# Sheet1.net
KiCad netlist of a schematic drawn in Altium Designer
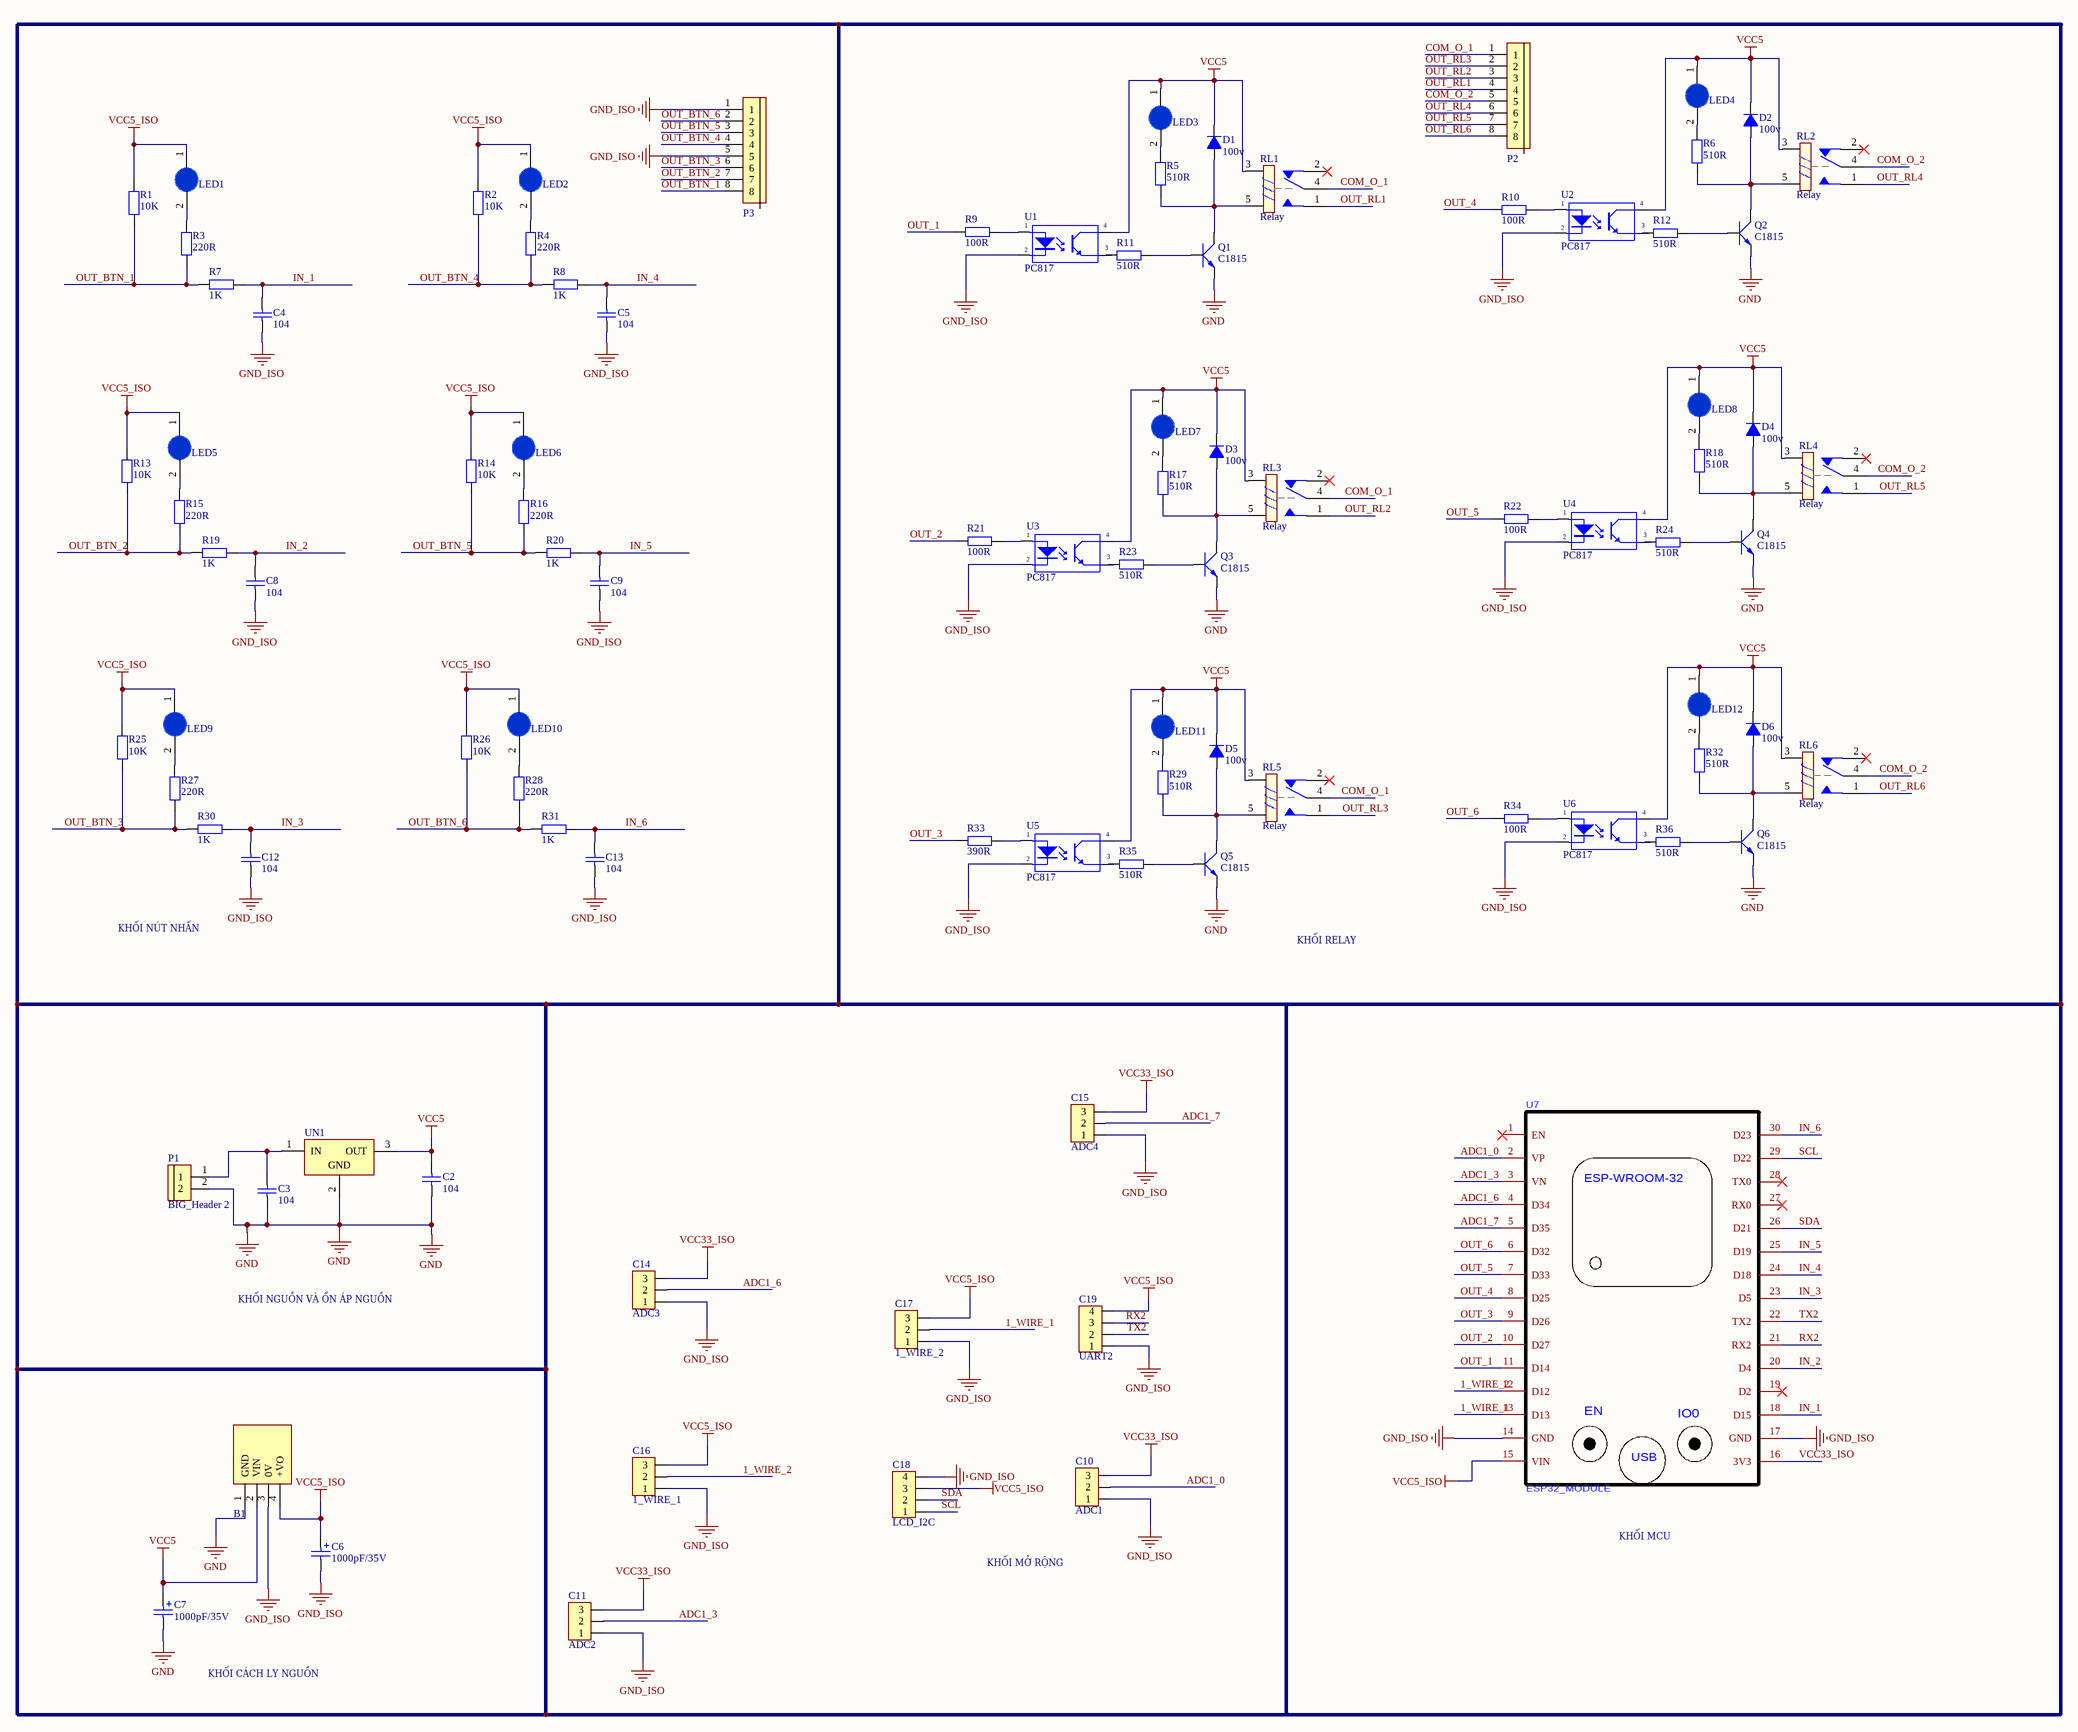
[diagram p0: Sheet1.SchDoc]

(export (version "E")
  (design (tool "Eeschema 10.0.6"))
  (components
    (comp (ref "B1")
      (value "B0505S1W")
      (footprint "B0505S1W")
      (description "Power Supply")
      (fields (field (name "MANUFACTURER_PART_NUMBER") "B0505S-1W"))
      (libsource (lib "myLib_v1") (part "B0505S1W"))
    )
    (comp (ref "C2")
      (value "104")
      (footprint "tu gom")
      (description "Cắm")
      (libsource (lib "Altium_Lib_by_KhueNguyenCreator") (part "Tu gom 104 50V"))
    )
    (comp (ref "C3")
      (value "104")
      (footprint "tu gom")
      (description "Cắm")
      (libsource (lib "Altium_Lib_by_KhueNguyenCreator") (part "Tu gom 104 50V"))
    )
    (comp (ref "C4")
      (value "104")
      (footprint "tu gom")
      (description "Cắm")
      (libsource (lib "Altium_Lib_by_KhueNguyenCreator") (part "Tu gom 104 50V"))
    )
    (comp (ref "C5")
      (value "104")
      (footprint "tu gom")
      (description "Cắm")
      (libsource (lib "Altium_Lib_by_KhueNguyenCreator") (part "Tu gom 104 50V"))
    )
    (comp (ref "C6")
      (value "1000pF/35V")
      (footprint "CP2/5")
      (description "Polarized Capacitor (Surface Mount)")
      (fields (field (name "Comment") "Cap Pol3") (field (name "PUBLISHER") "Altium Limited"))
      (libsource (lib "myLib_v1") (part "Cap Pol3"))
    )
    (comp (ref "C7")
      (value "1000pF/35V")
      (footprint "CP2/5")
      (description "Polarized Capacitor (Surface Mount)")
      (fields (field (name "Comment") "Cap Pol3") (field (name "PUBLISHER") "Altium Limited"))
      (libsource (lib "myLib_v1") (part "Cap Pol3"))
    )
    (comp (ref "C8")
      (value "104")
      (footprint "tu gom")
      (description "Cắm")
      (libsource (lib "Altium_Lib_by_KhueNguyenCreator") (part "Tu gom 104 50V"))
    )
    (comp (ref "C9")
      (value "104")
      (footprint "tu gom")
      (description "Cắm")
      (libsource (lib "Altium_Lib_by_KhueNguyenCreator") (part "Tu gom 104 50V"))
    )
    (comp (ref "C10")
      (value "ADC1")
      (footprint "Header3")
      (description "Header IDC, 3 x 1 Pin Vertical 2.54mm Pitch (Non-Boxed, Male)")
      (fields
        (field (name "MANUFACTURER") "Würth Elektronik eiSos GmbH")
        (field (name "PARTNO") "613002143121")
        (field (name "CREATED BY") "Karrer Zheng")
      )
      (libsource (lib "myLib_v1") (part "Header3"))
    )
    (comp (ref "C11")
      (value "ADC2")
      (footprint "Header3")
      (description "Header IDC, 3 x 1 Pin Vertical 2.54mm Pitch (Non-Boxed, Male)")
      (fields
        (field (name "MANUFACTURER") "Würth Elektronik eiSos GmbH")
        (field (name "PARTNO") "613002143121")
        (field (name "CREATED BY") "Karrer Zheng")
      )
      (libsource (lib "myLib_v1") (part "Header3"))
    )
    (comp (ref "C12")
      (value "104")
      (footprint "tu gom")
      (description "Cắm")
      (libsource (lib "Altium_Lib_by_KhueNguyenCreator") (part "Tu gom 104 50V"))
    )
    (comp (ref "C13")
      (value "104")
      (footprint "tu gom")
      (description "Cắm")
      (libsource (lib "Altium_Lib_by_KhueNguyenCreator") (part "Tu gom 104 50V"))
    )
    (comp (ref "C14")
      (value "ADC3")
      (footprint "Header3")
      (description "Header IDC, 3 x 1 Pin Vertical 2.54mm Pitch (Non-Boxed, Male)")
      (fields
        (field (name "MANUFACTURER") "Würth Elektronik eiSos GmbH")
        (field (name "PARTNO") "613002143121")
        (field (name "CREATED BY") "Karrer Zheng")
      )
      (libsource (lib "myLib_v1") (part "Header3"))
    )
    (comp (ref "C15")
      (value "ADC4")
      (footprint "Header3")
      (description "Header IDC, 3 x 1 Pin Vertical 2.54mm Pitch (Non-Boxed, Male)")
      (fields
        (field (name "MANUFACTURER") "Würth Elektronik eiSos GmbH")
        (field (name "PARTNO") "613002143121")
        (field (name "CREATED BY") "Karrer Zheng")
      )
      (libsource (lib "myLib_v1") (part "Header3"))
    )
    (comp (ref "C16")
      (value "1_WIRE_1")
      (footprint "Header3")
      (description "Header IDC, 3 x 1 Pin Vertical 2.54mm Pitch (Non-Boxed, Male)")
      (fields
        (field (name "MANUFACTURER") "Würth Elektronik eiSos GmbH")
        (field (name "PARTNO") "613002143121")
        (field (name "CREATED BY") "Karrer Zheng")
      )
      (libsource (lib "myLib_v1") (part "Header3"))
    )
    (comp (ref "C17")
      (value "1_WIRE_2")
      (footprint "Header3")
      (description "Header IDC, 3 x 1 Pin Vertical 2.54mm Pitch (Non-Boxed, Male)")
      (fields
        (field (name "MANUFACTURER") "Würth Elektronik eiSos GmbH")
        (field (name "PARTNO") "613002143121")
        (field (name "CREATED BY") "Karrer Zheng")
      )
      (libsource (lib "myLib_v1") (part "Header3"))
    )
    (comp (ref "C18")
      (value "LCD_I2C")
      (footprint "Header4")
      (description "Header IDC, 4 x 1 Pin Vertical 2.54mm Pitch (Non-Boxed, Male)")
      (fields
        (field (name "MANUFACTURER") "Würth Elektronik eiSos GmbH")
        (field (name "PARTNO") "613002143121")
        (field (name "CREATED BY") "Karrer Zheng")
      )
      (libsource (lib "myLib_v1") (part "Header4"))
    )
    (comp (ref "C19")
      (value "UART2")
      (footprint "Header4")
      (description "Header IDC, 4 x 1 Pin Vertical 2.54mm Pitch (Non-Boxed, Male)")
      (fields
        (field (name "MANUFACTURER") "Würth Elektronik eiSos GmbH")
        (field (name "PARTNO") "613002143121")
        (field (name "CREATED BY") "Karrer Zheng")
      )
      (libsource (lib "myLib_v1") (part "Header4"))
    )
    (comp (ref "D1")
      (value "100v")
      (footprint "DIODE 0.5A")
      (description "Cắm")
      (libsource (lib "Altium_Lib_by_KhueNguyenCreator") (part "Diode 1N4148"))
    )
    (comp (ref "D2")
      (value "100v")
      (footprint "DIODE 0.5A")
      (description "Cắm")
      (libsource (lib "Altium_Lib_by_KhueNguyenCreator") (part "Diode 1N4148"))
    )
    (comp (ref "D3")
      (value "100v")
      (footprint "DIODE 0.5A")
      (description "Cắm")
      (libsource (lib "Altium_Lib_by_KhueNguyenCreator") (part "Diode 1N4148"))
    )
    (comp (ref "D4")
      (value "100v")
      (footprint "DIODE 0.5A")
      (description "Cắm")
      (libsource (lib "Altium_Lib_by_KhueNguyenCreator") (part "Diode 1N4148"))
    )
    (comp (ref "D5")
      (value "100v")
      (footprint "DIODE 0.5A")
      (description "Cắm")
      (libsource (lib "Altium_Lib_by_KhueNguyenCreator") (part "Diode 1N4148"))
    )
    (comp (ref "D6")
      (value "100v")
      (footprint "DIODE 0.5A")
      (description "Cắm")
      (libsource (lib "Altium_Lib_by_KhueNguyenCreator") (part "Diode 1N4148"))
    )
    (comp (ref "LED1")
      (value "LED 3mm")
      (footprint "LED-3MM-BLUE")
      (description "Cắm")
      (libsource (lib "myLib_v1") (part "LED 3mm Xanh Duong"))
    )
    (comp (ref "LED2")
      (value "LED 3mm")
      (footprint "LED-3MM-BLUE")
      (description "Cắm")
      (libsource (lib "myLib_v1") (part "LED 3mm Xanh Duong"))
    )
    (comp (ref "LED3")
      (value "LED 3mm")
      (footprint "LED-3MM-BLUE")
      (description "Cắm")
      (libsource (lib "myLib_v1") (part "LED 3mm Xanh Duong"))
    )
    (comp (ref "LED4")
      (value "LED 3mm")
      (footprint "LED-3MM-BLUE")
      (description "Cắm")
      (libsource (lib "myLib_v1") (part "LED 3mm Xanh Duong"))
    )
    (comp (ref "LED5")
      (value "LED 3mm")
      (footprint "LED-3MM-BLUE")
      (description "Cắm")
      (libsource (lib "myLib_v1") (part "LED 3mm Xanh Duong"))
    )
    (comp (ref "LED6")
      (value "LED 3mm")
      (footprint "LED-3MM-BLUE")
      (description "Cắm")
      (libsource (lib "myLib_v1") (part "LED 3mm Xanh Duong"))
    )
    (comp (ref "LED7")
      (value "LED 3mm")
      (footprint "LED-3MM-BLUE")
      (description "Cắm")
      (libsource (lib "myLib_v1") (part "LED 3mm Xanh Duong"))
    )
    (comp (ref "LED8")
      (value "LED 3mm")
      (footprint "LED-3MM-BLUE")
      (description "Cắm")
      (libsource (lib "myLib_v1") (part "LED 3mm Xanh Duong"))
    )
    (comp (ref "LED9")
      (value "LED 3mm")
      (footprint "LED-3MM-BLUE")
      (description "Cắm")
      (libsource (lib "myLib_v1") (part "LED 3mm Xanh Duong"))
    )
    (comp (ref "LED10")
      (value "LED 3mm")
      (footprint "LED-3MM-BLUE")
      (description "Cắm")
      (libsource (lib "myLib_v1") (part "LED 3mm Xanh Duong"))
    )
    (comp (ref "LED11")
      (value "LED 3mm")
      (footprint "LED-3MM-BLUE")
      (description "Cắm")
      (libsource (lib "myLib_v1") (part "LED 3mm Xanh Duong"))
    )
    (comp (ref "LED12")
      (value "LED 3mm")
      (footprint "LED-3MM-BLUE")
      (description "Cắm")
      (libsource (lib "myLib_v1") (part "LED 3mm Xanh Duong"))
    )
    (comp (ref "P1")
      (value "BIG_Header 2")
      (footprint "BIG_Header 2")
      (libsource (lib "BYTECH_HW_LIB_2019 (1)") (part "BIG_Header 2"))
    )
    (comp (ref "P2")
      (value "BIG Heager 8")
      (footprint "BIG_Header 8")
      (libsource (lib "BYTECH_HW_LIB_2019 (1)") (part "BIG_Header 8"))
    )
    (comp (ref "P3")
      (value "BIG Heager 8")
      (footprint "BIG_Header 8")
      (libsource (lib "BYTECH_HW_LIB_2019 (1)") (part "BIG_Header 8"))
    )
    (comp (ref "Q1")
      (value "C1815")
      (footprint "C1815_cam")
      (description "NPN 600mW, ECB")
      (libsource (lib "myLib_v1") (part "C1815"))
    )
    (comp (ref "Q2")
      (value "C1815")
      (footprint "C1815_cam")
      (description "NPN 600mW, ECB")
      (libsource (lib "myLib_v1") (part "C1815"))
    )
    (comp (ref "Q3")
      (value "C1815")
      (footprint "C1815_cam")
      (description "NPN 600mW, ECB")
      (libsource (lib "myLib_v1") (part "C1815"))
    )
    (comp (ref "Q4")
      (value "C1815")
      (footprint "C1815_cam")
      (description "NPN 600mW, ECB")
      (libsource (lib "myLib_v1") (part "C1815"))
    )
    (comp (ref "Q5")
      (value "C1815")
      (footprint "C1815_cam")
      (description "NPN 600mW, ECB")
      (libsource (lib "myLib_v1") (part "C1815"))
    )
    (comp (ref "Q6")
      (value "C1815")
      (footprint "C1815_cam")
      (description "NPN 600mW, ECB")
      (libsource (lib "myLib_v1") (part "C1815"))
    )
    (comp (ref "R1")
      (value "10K")
      (footprint "R1/4W")
      (description "Resistor 1/4W")
      (libsource (lib "myLib_v1") (part "R1/4W"))
    )
    (comp (ref "R2")
      (value "10K")
      (footprint "R1/4W")
      (description "Resistor 1/4W")
      (libsource (lib "myLib_v1") (part "R1/4W"))
    )
    (comp (ref "R3")
      (value "220R")
      (footprint "R1/4W")
      (description "Resistor 1/4W")
      (libsource (lib "myLib_v1") (part "R1/4W"))
    )
    (comp (ref "R4")
      (value "220R")
      (footprint "R1/4W")
      (description "Resistor 1/4W")
      (libsource (lib "myLib_v1") (part "R1/4W"))
    )
    (comp (ref "R5")
      (value "510R")
      (footprint "R1/4W")
      (description "Resistor 1/4W")
      (libsource (lib "myLib_v1") (part "R1/4W"))
    )
    (comp (ref "R6")
      (value "510R")
      (footprint "R1/4W")
      (description "Resistor 1/4W")
      (libsource (lib "myLib_v1") (part "R1/4W"))
    )
    (comp (ref "R7")
      (value "1K")
      (footprint "R1/4W")
      (description "Resistor 1/4W")
      (libsource (lib "myLib_v1") (part "R1/4W"))
    )
    (comp (ref "R8")
      (value "1K")
      (footprint "R1/4W")
      (description "Resistor 1/4W")
      (libsource (lib "myLib_v1") (part "R1/4W"))
    )
    (comp (ref "R9")
      (value "100R")
      (footprint "R1/4W")
      (description "Resistor 1/4W")
      (libsource (lib "myLib_v1") (part "R1/4W"))
    )
    (comp (ref "R10")
      (value "100R")
      (footprint "R1/4W")
      (description "Resistor 1/4W")
      (libsource (lib "myLib_v1") (part "R1/4W"))
    )
    (comp (ref "R11")
      (value "510R")
      (footprint "R1/4W")
      (description "Resistor 1/4W")
      (libsource (lib "myLib_v1") (part "R1/4W"))
    )
    (comp (ref "R12")
      (value "510R")
      (footprint "R1/4W")
      (description "Resistor 1/4W")
      (libsource (lib "myLib_v1") (part "R1/4W"))
    )
    (comp (ref "R13")
      (value "10K")
      (footprint "R1/4W")
      (description "Resistor 1/4W")
      (libsource (lib "myLib_v1") (part "R1/4W"))
    )
    (comp (ref "R14")
      (value "10K")
      (footprint "R1/4W")
      (description "Resistor 1/4W")
      (libsource (lib "myLib_v1") (part "R1/4W"))
    )
    (comp (ref "R15")
      (value "220R")
      (footprint "R1/4W")
      (description "Resistor 1/4W")
      (libsource (lib "myLib_v1") (part "R1/4W"))
    )
    (comp (ref "R16")
      (value "220R")
      (footprint "R1/4W")
      (description "Resistor 1/4W")
      (libsource (lib "myLib_v1") (part "R1/4W"))
    )
    (comp (ref "R17")
      (value "510R")
      (footprint "R1/4W")
      (description "Resistor 1/4W")
      (libsource (lib "myLib_v1") (part "R1/4W"))
    )
    (comp (ref "R18")
      (value "510R")
      (footprint "R1/4W")
      (description "Resistor 1/4W")
      (libsource (lib "myLib_v1") (part "R1/4W"))
    )
    (comp (ref "R19")
      (value "1K")
      (footprint "R1/4W")
      (description "Resistor 1/4W")
      (libsource (lib "myLib_v1") (part "R1/4W"))
    )
    (comp (ref "R20")
      (value "1K")
      (footprint "R1/4W")
      (description "Resistor 1/4W")
      (libsource (lib "myLib_v1") (part "R1/4W"))
    )
    (comp (ref "R21")
      (value "100R")
      (footprint "R1/4W")
      (description "Resistor 1/4W")
      (libsource (lib "myLib_v1") (part "R1/4W"))
    )
    (comp (ref "R22")
      (value "100R")
      (footprint "R1/4W")
      (description "Resistor 1/4W")
      (libsource (lib "myLib_v1") (part "R1/4W"))
    )
    (comp (ref "R23")
      (value "510R")
      (footprint "R1/4W")
      (description "Resistor 1/4W")
      (libsource (lib "myLib_v1") (part "R1/4W"))
    )
    (comp (ref "R24")
      (value "510R")
      (footprint "R1/4W")
      (description "Resistor 1/4W")
      (libsource (lib "myLib_v1") (part "R1/4W"))
    )
    (comp (ref "R25")
      (value "10K")
      (footprint "R1/4W")
      (description "Resistor 1/4W")
      (libsource (lib "myLib_v1") (part "R1/4W"))
    )
    (comp (ref "R26")
      (value "10K")
      (footprint "R1/4W")
      (description "Resistor 1/4W")
      (libsource (lib "myLib_v1") (part "R1/4W"))
    )
    (comp (ref "R27")
      (value "220R")
      (footprint "R1/4W")
      (description "Resistor 1/4W")
      (libsource (lib "myLib_v1") (part "R1/4W"))
    )
    (comp (ref "R28")
      (value "220R")
      (footprint "R1/4W")
      (description "Resistor 1/4W")
      (libsource (lib "myLib_v1") (part "R1/4W"))
    )
    (comp (ref "R29")
      (value "510R")
      (footprint "R1/4W")
      (description "Resistor 1/4W")
      (libsource (lib "myLib_v1") (part "R1/4W"))
    )
    (comp (ref "R30")
      (value "1K")
      (footprint "R1/4W")
      (description "Resistor 1/4W")
      (libsource (lib "myLib_v1") (part "R1/4W"))
    )
    (comp (ref "R31")
      (value "1K")
      (footprint "R1/4W")
      (description "Resistor 1/4W")
      (libsource (lib "myLib_v1") (part "R1/4W"))
    )
    (comp (ref "R32")
      (value "510R")
      (footprint "R1/4W")
      (description "Resistor 1/4W")
      (libsource (lib "myLib_v1") (part "R1/4W"))
    )
    (comp (ref "R33")
      (value "390R")
      (footprint "R1/4W")
      (description "Resistor 1/4W")
      (libsource (lib "myLib_v1") (part "R1/4W"))
    )
    (comp (ref "R34")
      (value "100R")
      (footprint "R1/4W")
      (description "Resistor 1/4W")
      (libsource (lib "myLib_v1") (part "R1/4W"))
    )
    (comp (ref "R35")
      (value "510R")
      (footprint "R1/4W")
      (description "Resistor 1/4W")
      (libsource (lib "myLib_v1") (part "R1/4W"))
    )
    (comp (ref "R36")
      (value "510R")
      (footprint "R1/4W")
      (description "Resistor 1/4W")
      (libsource (lib "myLib_v1") (part "R1/4W"))
    )
    (comp (ref "RL1")
      (value "Relay")
      (footprint "RELAY_SRA_05VDC_SL_C")
      (description "Relay 5 Chan")
      (libsource (lib "myLib_v1") (part "RL_SRA-05VDC-SL-C"))
    )
    (comp (ref "RL2")
      (value "Relay")
      (footprint "RELAY_SRA_05VDC_SL_C")
      (description "Relay 5 Chan")
      (libsource (lib "myLib_v1") (part "RL_SRA-05VDC-SL-C"))
    )
    (comp (ref "RL3")
      (value "Relay")
      (footprint "RELAY_SRA_05VDC_SL_C")
      (description "Relay 5 Chan")
      (libsource (lib "myLib_v1") (part "RL_SRA-05VDC-SL-C"))
    )
    (comp (ref "RL4")
      (value "Relay")
      (footprint "RELAY_SRA_05VDC_SL_C")
      (description "Relay 5 Chan")
      (libsource (lib "myLib_v1") (part "RL_SRA-05VDC-SL-C"))
    )
    (comp (ref "RL5")
      (value "Relay")
      (footprint "RELAY_SRA_05VDC_SL_C")
      (description "Relay 5 Chan")
      (libsource (lib "myLib_v1") (part "RL_SRA-05VDC-SL-C"))
    )
    (comp (ref "RL6")
      (value "Relay")
      (footprint "RELAY_SRA_05VDC_SL_C")
      (description "Relay 5 Chan")
      (libsource (lib "myLib_v1") (part "RL_SRA-05VDC-SL-C"))
    )
    (comp (ref "U1")
      (value "PC817")
      (footprint "DIP4/W0.3")
      (description "Single Opto")
      (libsource (lib "myLib_v1") (part "PC817"))
    )
    (comp (ref "U2")
      (value "PC817")
      (footprint "DIP4/W0.3")
      (description "Single Opto")
      (libsource (lib "myLib_v1") (part "PC817"))
    )
    (comp (ref "U3")
      (value "PC817")
      (footprint "DIP4/W0.3")
      (description "Single Opto")
      (libsource (lib "myLib_v1") (part "PC817"))
    )
    (comp (ref "U4")
      (value "PC817")
      (footprint "DIP4/W0.3")
      (description "Single Opto")
      (libsource (lib "myLib_v1") (part "PC817"))
    )
    (comp (ref "U5")
      (value "PC817")
      (footprint "DIP4/W0.3")
      (description "Single Opto")
      (libsource (lib "myLib_v1") (part "PC817"))
    )
    (comp (ref "U6")
      (value "PC817")
      (footprint "DIP4/W0.3")
      (description "Single Opto")
      (libsource (lib "myLib_v1") (part "PC817"))
    )
    (comp (ref "U7")
      (value "ESP32_MODULE")
      (footprint "ESP32-WIFIMODULE-FOOTPRINT")
      (libsource (lib "myLib_v1") (part "ESP32_MODULE copy"))
    )
    (comp (ref "UN1")
      (value "L78M05CP")
      (footprint "QTO-220H2")
      (description "Positive Voltage Regulator")
      (fields (field (name "PUBLISHER") "Altium Limited"))
      (libsource (lib "syhaunguyen") (part "L78M05CP"))
    )
  )
  (nets
    (net (code "1") (name "/1_WIRE_1") (class "Default")
      (node (ref "C17") (pin "2") (pinfunction "2_2") (pintype "passive"))
      (node (ref "U7") (pin "13") (pinfunction "D13_13") (pintype "passive"))
    )
    (net (code "2") (name "/1_WIRE_2") (class "Default")
      (node (ref "C16") (pin "2") (pinfunction "2_2") (pintype "passive"))
      (node (ref "U7") (pin "12") (pinfunction "D12_12") (pintype "passive"))
    )
    (net (code "3") (name "/ADC1_0") (class "Default")
      (node (ref "C10") (pin "2") (pinfunction "2_2") (pintype "passive"))
      (node (ref "U7") (pin "2") (pinfunction "VP_2") (pintype "passive"))
    )
    (net (code "4") (name "/ADC1_3") (class "Default")
      (node (ref "C11") (pin "2") (pinfunction "2_2") (pintype "passive"))
      (node (ref "U7") (pin "3") (pinfunction "VN_3") (pintype "passive"))
    )
    (net (code "5") (name "/ADC1_6") (class "Default")
      (node (ref "C14") (pin "2") (pinfunction "2_2") (pintype "passive"))
      (node (ref "U7") (pin "4") (pinfunction "D34_4") (pintype "passive"))
    )
    (net (code "6") (name "/ADC1_7") (class "Default")
      (node (ref "C15") (pin "2") (pinfunction "2_2") (pintype "passive"))
      (node (ref "U7") (pin "5") (pinfunction "D35_5") (pintype "passive"))
    )
    (net (code "7") (name "/COM_O_1") (class "Default")
      (node (ref "P2") (pin "1") (pinfunction "1_1") (pintype "passive"))
      (node (ref "RL1") (pin "4") (pinfunction "4_4") (pintype "passive"))
      (node (ref "RL3") (pin "4") (pinfunction "4_4") (pintype "passive"))
      (node (ref "RL5") (pin "4") (pinfunction "4_4") (pintype "passive"))
    )
    (net (code "8") (name "/COM_O_2") (class "Default")
      (node (ref "P2") (pin "5") (pinfunction "5_5") (pintype "passive"))
      (node (ref "RL2") (pin "4") (pinfunction "4_4") (pintype "passive"))
      (node (ref "RL4") (pin "4") (pinfunction "4_4") (pintype "passive"))
      (node (ref "RL6") (pin "4") (pinfunction "4_4") (pintype "passive"))
    )
    (net (code "9") (name "/IN_1") (class "Default")
      (node (ref "C4") (pin "1") (pinfunction "1_1") (pintype "passive"))
      (node (ref "R7") (pin "1") (pinfunction "1_1") (pintype "passive"))
      (node (ref "U7") (pin "18") (pinfunction "D15_18") (pintype "passive"))
    )
    (net (code "10") (name "/IN_2") (class "Default")
      (node (ref "C8") (pin "1") (pinfunction "1_1") (pintype "passive"))
      (node (ref "R19") (pin "1") (pinfunction "1_1") (pintype "passive"))
      (node (ref "U7") (pin "20") (pinfunction "D4_20") (pintype "passive"))
    )
    (net (code "11") (name "/IN_3") (class "Default")
      (node (ref "C12") (pin "1") (pinfunction "1_1") (pintype "passive"))
      (node (ref "R30") (pin "1") (pinfunction "1_1") (pintype "passive"))
      (node (ref "U7") (pin "23") (pinfunction "D5_23") (pintype "passive"))
    )
    (net (code "12") (name "/IN_4") (class "Default")
      (node (ref "C5") (pin "1") (pinfunction "1_1") (pintype "passive"))
      (node (ref "R8") (pin "1") (pinfunction "1_1") (pintype "passive"))
      (node (ref "U7") (pin "24") (pinfunction "D18_24") (pintype "passive"))
    )
    (net (code "13") (name "/IN_5") (class "Default")
      (node (ref "C9") (pin "1") (pinfunction "1_1") (pintype "passive"))
      (node (ref "R20") (pin "1") (pinfunction "1_1") (pintype "passive"))
      (node (ref "U7") (pin "25") (pinfunction "D19_25") (pintype "passive"))
    )
    (net (code "14") (name "/IN_6") (class "Default")
      (node (ref "C13") (pin "1") (pinfunction "1_1") (pintype "passive"))
      (node (ref "R31") (pin "1") (pinfunction "1_1") (pintype "passive"))
      (node (ref "U7") (pin "30") (pinfunction "D23_30") (pintype "passive"))
    )
    (net (code "15") (name "/OUT_1") (class "Default")
      (node (ref "R9") (pin "1") (pinfunction "1_1") (pintype "passive"))
      (node (ref "U7") (pin "11") (pinfunction "D14_11") (pintype "passive"))
    )
    (net (code "16") (name "/OUT_2") (class "Default")
      (node (ref "R21") (pin "1") (pinfunction "1_1") (pintype "passive"))
      (node (ref "U7") (pin "10") (pinfunction "D27_10") (pintype "passive"))
    )
    (net (code "17") (name "/OUT_3") (class "Default")
      (node (ref "R33") (pin "1") (pinfunction "1_1") (pintype "passive"))
      (node (ref "U7") (pin "9") (pinfunction "D26_9") (pintype "passive"))
    )
    (net (code "18") (name "/OUT_4") (class "Default")
      (node (ref "R10") (pin "1") (pinfunction "1_1") (pintype "passive"))
      (node (ref "U7") (pin "8") (pinfunction "D25_8") (pintype "passive"))
    )
    (net (code "19") (name "/OUT_5") (class "Default")
      (node (ref "R22") (pin "1") (pinfunction "1_1") (pintype "passive"))
      (node (ref "U7") (pin "7") (pinfunction "D33_7") (pintype "passive"))
    )
    (net (code "20") (name "/OUT_6") (class "Default")
      (node (ref "R34") (pin "1") (pinfunction "1_1") (pintype "passive"))
      (node (ref "U7") (pin "6") (pinfunction "D32_6") (pintype "passive"))
    )
    (net (code "21") (name "/OUT_BTN_1") (class "Default")
      (node (ref "P3") (pin "8") (pinfunction "8_8") (pintype "passive"))
      (node (ref "R1") (pin "1") (pinfunction "1_1") (pintype "passive"))
      (node (ref "R3") (pin "1") (pinfunction "1_1") (pintype "passive"))
      (node (ref "R7") (pin "2") (pinfunction "2_2") (pintype "passive"))
    )
    (net (code "22") (name "/OUT_BTN_2") (class "Default")
      (node (ref "P3") (pin "7") (pinfunction "7_7") (pintype "passive"))
      (node (ref "R13") (pin "1") (pinfunction "1_1") (pintype "passive"))
      (node (ref "R15") (pin "1") (pinfunction "1_1") (pintype "passive"))
      (node (ref "R19") (pin "2") (pinfunction "2_2") (pintype "passive"))
    )
    (net (code "23") (name "/OUT_BTN_3") (class "Default")
      (node (ref "P3") (pin "6") (pinfunction "6_6") (pintype "passive"))
      (node (ref "R25") (pin "1") (pinfunction "1_1") (pintype "passive"))
      (node (ref "R27") (pin "1") (pinfunction "1_1") (pintype "passive"))
      (node (ref "R30") (pin "2") (pinfunction "2_2") (pintype "passive"))
    )
    (net (code "24") (name "/OUT_BTN_4") (class "Default")
      (node (ref "P3") (pin "4") (pinfunction "4_4") (pintype "passive"))
      (node (ref "R2") (pin "1") (pinfunction "1_1") (pintype "passive"))
      (node (ref "R4") (pin "1") (pinfunction "1_1") (pintype "passive"))
      (node (ref "R8") (pin "2") (pinfunction "2_2") (pintype "passive"))
    )
    (net (code "25") (name "/OUT_BTN_5") (class "Default")
      (node (ref "P3") (pin "3") (pinfunction "3_3") (pintype "passive"))
      (node (ref "R14") (pin "1") (pinfunction "1_1") (pintype "passive"))
      (node (ref "R16") (pin "1") (pinfunction "1_1") (pintype "passive"))
      (node (ref "R20") (pin "2") (pinfunction "2_2") (pintype "passive"))
    )
    (net (code "26") (name "/OUT_BTN_6") (class "Default")
      (node (ref "P3") (pin "2") (pinfunction "2_2") (pintype "passive"))
      (node (ref "R26") (pin "1") (pinfunction "1_1") (pintype "passive"))
      (node (ref "R28") (pin "1") (pinfunction "1_1") (pintype "passive"))
      (node (ref "R31") (pin "2") (pinfunction "2_2") (pintype "passive"))
    )
    (net (code "27") (name "/OUT_RL1") (class "Default")
      (node (ref "P2") (pin "4") (pinfunction "4_4") (pintype "passive"))
      (node (ref "RL1") (pin "1") (pinfunction "1_1") (pintype "passive"))
    )
    (net (code "28") (name "/OUT_RL2") (class "Default")
      (node (ref "P2") (pin "3") (pinfunction "3_3") (pintype "passive"))
      (node (ref "RL3") (pin "1") (pinfunction "1_1") (pintype "passive"))
    )
    (net (code "29") (name "/OUT_RL3") (class "Default")
      (node (ref "P2") (pin "2") (pinfunction "2_2") (pintype "passive"))
      (node (ref "RL5") (pin "1") (pinfunction "1_1") (pintype "passive"))
    )
    (net (code "30") (name "/OUT_RL4") (class "Default")
      (node (ref "P2") (pin "6") (pinfunction "6_6") (pintype "passive"))
      (node (ref "RL2") (pin "1") (pinfunction "1_1") (pintype "passive"))
    )
    (net (code "31") (name "/OUT_RL5") (class "Default")
      (node (ref "P2") (pin "7") (pinfunction "7_7") (pintype "passive"))
      (node (ref "RL4") (pin "1") (pinfunction "1_1") (pintype "passive"))
    )
    (net (code "32") (name "/OUT_RL6") (class "Default")
      (node (ref "P2") (pin "8") (pinfunction "8_8") (pintype "passive"))
      (node (ref "RL6") (pin "1") (pinfunction "1_1") (pintype "passive"))
    )
    (net (code "33") (name "/RX2") (class "Default")
      (node (ref "C19") (pin "3") (pinfunction "3_3") (pintype "passive"))
      (node (ref "U7") (pin "21") (pinfunction "RX2_21") (pintype "passive"))
    )
    (net (code "34") (name "/SCL") (class "Default")
      (node (ref "C18") (pin "1") (pinfunction "1_1") (pintype "passive"))
      (node (ref "U7") (pin "29") (pinfunction "D22_29") (pintype "passive"))
    )
    (net (code "35") (name "/SDA") (class "Default")
      (node (ref "C18") (pin "2") (pinfunction "2_2") (pintype "passive"))
      (node (ref "U7") (pin "26") (pinfunction "D21_26") (pintype "passive"))
    )
    (net (code "36") (name "/TX2") (class "Default")
      (node (ref "C19") (pin "2") (pinfunction "2_2") (pintype "passive"))
      (node (ref "U7") (pin "22") (pinfunction "TX2_22") (pintype "passive"))
    )
    (net (code "37") (name "GND") (class "Default")
      (node (ref "B1") (pin "1") (pinfunction "GND_1") (pintype "passive"))
      (node (ref "C2") (pin "2") (pinfunction "2_2") (pintype "passive"))
      (node (ref "C3") (pin "2") (pinfunction "2_2") (pintype "passive"))
      (node (ref "C7") (pin "2") (pinfunction "2_2") (pintype "passive"))
      (node (ref "P1") (pin "2") (pinfunction "2_2") (pintype "passive"))
      (node (ref "Q1") (pin "1") (pinfunction "E_1") (pintype "passive"))
      (node (ref "Q2") (pin "1") (pinfunction "E_1") (pintype "passive"))
      (node (ref "Q3") (pin "1") (pinfunction "E_1") (pintype "passive"))
      (node (ref "Q4") (pin "1") (pinfunction "E_1") (pintype "passive"))
      (node (ref "Q5") (pin "1") (pinfunction "E_1") (pintype "passive"))
      (node (ref "Q6") (pin "1") (pinfunction "E_1") (pintype "passive"))
      (node (ref "UN1") (pin "2") (pinfunction "GND_2") (pintype "power_in"))
    )
    (net (code "38") (name "GND_ISO") (class "Default")
      (node (ref "B1") (pin "3") (pinfunction "0V_3") (pintype "passive"))
      (node (ref "C10") (pin "1") (pinfunction "1_1") (pintype "passive"))
      (node (ref "C11") (pin "1") (pinfunction "1_1") (pintype "passive"))
      (node (ref "C12") (pin "2") (pinfunction "2_2") (pintype "passive"))
      (node (ref "C13") (pin "2") (pinfunction "2_2") (pintype "passive"))
      (node (ref "C14") (pin "1") (pinfunction "1_1") (pintype "passive"))
      (node (ref "C15") (pin "1") (pinfunction "1_1") (pintype "passive"))
      (node (ref "C16") (pin "1") (pinfunction "1_1") (pintype "passive"))
      (node (ref "C17") (pin "1") (pinfunction "1_1") (pintype "passive"))
      (node (ref "C18") (pin "4") (pinfunction "4_4") (pintype "passive"))
      (node (ref "C19") (pin "1") (pinfunction "1_1") (pintype "passive"))
      (node (ref "C4") (pin "2") (pinfunction "2_2") (pintype "passive"))
      (node (ref "C5") (pin "2") (pinfunction "2_2") (pintype "passive"))
      (node (ref "C6") (pin "2") (pinfunction "2_2") (pintype "passive"))
      (node (ref "C8") (pin "2") (pinfunction "2_2") (pintype "passive"))
      (node (ref "C9") (pin "2") (pinfunction "2_2") (pintype "passive"))
      (node (ref "P3") (pin "1") (pinfunction "1_1") (pintype "passive"))
      (node (ref "P3") (pin "5") (pinfunction "5_5") (pintype "passive"))
      (node (ref "U1") (pin "2") (pinfunction "K_2") (pintype "passive"))
      (node (ref "U2") (pin "2") (pinfunction "K_2") (pintype "passive"))
      (node (ref "U3") (pin "2") (pinfunction "K_2") (pintype "passive"))
      (node (ref "U4") (pin "2") (pinfunction "K_2") (pintype "passive"))
      (node (ref "U5") (pin "2") (pinfunction "K_2") (pintype "passive"))
      (node (ref "U6") (pin "2") (pinfunction "K_2") (pintype "passive"))
      (node (ref "U7") (pin "14") (pinfunction "GND_14") (pintype "passive"))
      (node (ref "U7") (pin "17") (pinfunction "GND_17") (pintype "passive"))
    )
    (net (code "39") (name "Net-(D1-A)") (class "Default")
      (node (ref "D1") (pin "1") (pinfunction "A_1") (pintype "passive"))
      (node (ref "Q1") (pin "2") (pinfunction "C_2") (pintype "passive"))
      (node (ref "R5") (pin "2") (pinfunction "2_2") (pintype "passive"))
      (node (ref "RL1") (pin "5") (pinfunction "5_5") (pintype "passive"))
    )
    (net (code "40") (name "Net-(D2-A)") (class "Default")
      (node (ref "D2") (pin "1") (pinfunction "A_1") (pintype "passive"))
      (node (ref "Q2") (pin "2") (pinfunction "C_2") (pintype "passive"))
      (node (ref "R6") (pin "2") (pinfunction "2_2") (pintype "passive"))
      (node (ref "RL2") (pin "5") (pinfunction "5_5") (pintype "passive"))
    )
    (net (code "41") (name "Net-(D3-A)") (class "Default")
      (node (ref "D3") (pin "1") (pinfunction "A_1") (pintype "passive"))
      (node (ref "Q3") (pin "2") (pinfunction "C_2") (pintype "passive"))
      (node (ref "R17") (pin "2") (pinfunction "2_2") (pintype "passive"))
      (node (ref "RL3") (pin "5") (pinfunction "5_5") (pintype "passive"))
    )
    (net (code "42") (name "Net-(D4-A)") (class "Default")
      (node (ref "D4") (pin "1") (pinfunction "A_1") (pintype "passive"))
      (node (ref "Q4") (pin "2") (pinfunction "C_2") (pintype "passive"))
      (node (ref "R18") (pin "2") (pinfunction "2_2") (pintype "passive"))
      (node (ref "RL4") (pin "5") (pinfunction "5_5") (pintype "passive"))
    )
    (net (code "43") (name "Net-(D5-A)") (class "Default")
      (node (ref "D5") (pin "1") (pinfunction "A_1") (pintype "passive"))
      (node (ref "Q5") (pin "2") (pinfunction "C_2") (pintype "passive"))
      (node (ref "R29") (pin "2") (pinfunction "2_2") (pintype "passive"))
      (node (ref "RL5") (pin "5") (pinfunction "5_5") (pintype "passive"))
    )
    (net (code "44") (name "Net-(D6-A)") (class "Default")
      (node (ref "D6") (pin "1") (pinfunction "A_1") (pintype "passive"))
      (node (ref "Q6") (pin "2") (pinfunction "C_2") (pintype "passive"))
      (node (ref "R32") (pin "2") (pinfunction "2_2") (pintype "passive"))
      (node (ref "RL6") (pin "5") (pinfunction "5_5") (pintype "passive"))
    )
    (net (code "45") (name "Net-(LED1-K)") (class "Default")
      (node (ref "LED1") (pin "2") (pinfunction "K_2") (pintype "passive"))
      (node (ref "R3") (pin "2") (pinfunction "2_2") (pintype "passive"))
    )
    (net (code "46") (name "Net-(LED2-K)") (class "Default")
      (node (ref "LED2") (pin "2") (pinfunction "K_2") (pintype "passive"))
      (node (ref "R4") (pin "2") (pinfunction "2_2") (pintype "passive"))
    )
    (net (code "47") (name "Net-(LED3-K)") (class "Default")
      (node (ref "LED3") (pin "2") (pinfunction "K_2") (pintype "passive"))
      (node (ref "R5") (pin "1") (pinfunction "1_1") (pintype "passive"))
    )
    (net (code "48") (name "Net-(LED4-K)") (class "Default")
      (node (ref "LED4") (pin "2") (pinfunction "K_2") (pintype "passive"))
      (node (ref "R6") (pin "1") (pinfunction "1_1") (pintype "passive"))
    )
    (net (code "49") (name "Net-(LED5-K)") (class "Default")
      (node (ref "LED5") (pin "2") (pinfunction "K_2") (pintype "passive"))
      (node (ref "R15") (pin "2") (pinfunction "2_2") (pintype "passive"))
    )
    (net (code "50") (name "Net-(LED6-K)") (class "Default")
      (node (ref "LED6") (pin "2") (pinfunction "K_2") (pintype "passive"))
      (node (ref "R16") (pin "2") (pinfunction "2_2") (pintype "passive"))
    )
    (net (code "51") (name "Net-(LED7-K)") (class "Default")
      (node (ref "LED7") (pin "2") (pinfunction "K_2") (pintype "passive"))
      (node (ref "R17") (pin "1") (pinfunction "1_1") (pintype "passive"))
    )
    (net (code "52") (name "Net-(LED8-K)") (class "Default")
      (node (ref "LED8") (pin "2") (pinfunction "K_2") (pintype "passive"))
      (node (ref "R18") (pin "1") (pinfunction "1_1") (pintype "passive"))
    )
    (net (code "53") (name "Net-(LED9-K)") (class "Default")
      (node (ref "LED9") (pin "2") (pinfunction "K_2") (pintype "passive"))
      (node (ref "R27") (pin "2") (pinfunction "2_2") (pintype "passive"))
    )
    (net (code "54") (name "Net-(LED10-K)") (class "Default")
      (node (ref "LED10") (pin "2") (pinfunction "K_2") (pintype "passive"))
      (node (ref "R28") (pin "2") (pinfunction "2_2") (pintype "passive"))
    )
    (net (code "55") (name "Net-(LED11-K)") (class "Default")
      (node (ref "LED11") (pin "2") (pinfunction "K_2") (pintype "passive"))
      (node (ref "R29") (pin "1") (pinfunction "1_1") (pintype "passive"))
    )
    (net (code "56") (name "Net-(LED12-K)") (class "Default")
      (node (ref "LED12") (pin "2") (pinfunction "K_2") (pintype "passive"))
      (node (ref "R32") (pin "1") (pinfunction "1_1") (pintype "passive"))
    )
    (net (code "57") (name "Net-(Q1-B)") (class "Default")
      (node (ref "Q1") (pin "3") (pinfunction "B_3") (pintype "passive"))
      (node (ref "R11") (pin "2") (pinfunction "2_2") (pintype "passive"))
    )
    (net (code "58") (name "Net-(Q2-B)") (class "Default")
      (node (ref "Q2") (pin "3") (pinfunction "B_3") (pintype "passive"))
      (node (ref "R12") (pin "2") (pinfunction "2_2") (pintype "passive"))
    )
    (net (code "59") (name "Net-(Q3-B)") (class "Default")
      (node (ref "Q3") (pin "3") (pinfunction "B_3") (pintype "passive"))
      (node (ref "R23") (pin "2") (pinfunction "2_2") (pintype "passive"))
    )
    (net (code "60") (name "Net-(Q4-B)") (class "Default")
      (node (ref "Q4") (pin "3") (pinfunction "B_3") (pintype "passive"))
      (node (ref "R24") (pin "2") (pinfunction "2_2") (pintype "passive"))
    )
    (net (code "61") (name "Net-(Q5-B)") (class "Default")
      (node (ref "Q5") (pin "3") (pinfunction "B_3") (pintype "passive"))
      (node (ref "R35") (pin "2") (pinfunction "2_2") (pintype "passive"))
    )
    (net (code "62") (name "Net-(Q6-B)") (class "Default")
      (node (ref "Q6") (pin "3") (pinfunction "B_3") (pintype "passive"))
      (node (ref "R36") (pin "2") (pinfunction "2_2") (pintype "passive"))
    )
    (net (code "63") (name "Net-(U1-A)") (class "Default")
      (node (ref "R9") (pin "2") (pinfunction "2_2") (pintype "passive"))
      (node (ref "U1") (pin "1") (pinfunction "A_1") (pintype "passive"))
    )
    (net (code "64") (name "Net-(U1-E)") (class "Default")
      (node (ref "R11") (pin "1") (pinfunction "1_1") (pintype "passive"))
      (node (ref "U1") (pin "3") (pinfunction "E_3") (pintype "passive"))
    )
    (net (code "65") (name "Net-(U2-A)") (class "Default")
      (node (ref "R10") (pin "2") (pinfunction "2_2") (pintype "passive"))
      (node (ref "U2") (pin "1") (pinfunction "A_1") (pintype "passive"))
    )
    (net (code "66") (name "Net-(U2-E)") (class "Default")
      (node (ref "R12") (pin "1") (pinfunction "1_1") (pintype "passive"))
      (node (ref "U2") (pin "3") (pinfunction "E_3") (pintype "passive"))
    )
    (net (code "67") (name "Net-(U3-A)") (class "Default")
      (node (ref "R21") (pin "2") (pinfunction "2_2") (pintype "passive"))
      (node (ref "U3") (pin "1") (pinfunction "A_1") (pintype "passive"))
    )
    (net (code "68") (name "Net-(U3-E)") (class "Default")
      (node (ref "R23") (pin "1") (pinfunction "1_1") (pintype "passive"))
      (node (ref "U3") (pin "3") (pinfunction "E_3") (pintype "passive"))
    )
    (net (code "69") (name "Net-(U4-A)") (class "Default")
      (node (ref "R22") (pin "2") (pinfunction "2_2") (pintype "passive"))
      (node (ref "U4") (pin "1") (pinfunction "A_1") (pintype "passive"))
    )
    (net (code "70") (name "Net-(U4-E)") (class "Default")
      (node (ref "R24") (pin "1") (pinfunction "1_1") (pintype "passive"))
      (node (ref "U4") (pin "3") (pinfunction "E_3") (pintype "passive"))
    )
    (net (code "71") (name "Net-(U5-A)") (class "Default")
      (node (ref "R33") (pin "2") (pinfunction "2_2") (pintype "passive"))
      (node (ref "U5") (pin "1") (pinfunction "A_1") (pintype "passive"))
    )
    (net (code "72") (name "Net-(U5-E)") (class "Default")
      (node (ref "R35") (pin "1") (pinfunction "1_1") (pintype "passive"))
      (node (ref "U5") (pin "3") (pinfunction "E_3") (pintype "passive"))
    )
    (net (code "73") (name "Net-(U6-A)") (class "Default")
      (node (ref "R34") (pin "2") (pinfunction "2_2") (pintype "passive"))
      (node (ref "U6") (pin "1") (pinfunction "A_1") (pintype "passive"))
    )
    (net (code "74") (name "Net-(U6-E)") (class "Default")
      (node (ref "R36") (pin "1") (pinfunction "1_1") (pintype "passive"))
      (node (ref "U6") (pin "3") (pinfunction "E_3") (pintype "passive"))
    )
    (net (code "75") (name "Net-(UN1-IN)") (class "Default")
      (node (ref "C3") (pin "1") (pinfunction "1_1") (pintype "passive"))
      (node (ref "P1") (pin "1") (pinfunction "1_1") (pintype "passive"))
      (node (ref "UN1") (pin "1") (pinfunction "IN_1") (pintype "power_in"))
    )
    (net (code "76") (name "VCC5") (class "Default")
      (node (ref "B1") (pin "2") (pinfunction "VIN_2") (pintype "passive"))
      (node (ref "C2") (pin "1") (pinfunction "1_1") (pintype "passive"))
      (node (ref "C7") (pin "1") (pinfunction "1_1") (pintype "passive"))
      (node (ref "D1") (pin "2") (pinfunction "K_2") (pintype "passive"))
      (node (ref "D2") (pin "2") (pinfunction "K_2") (pintype "passive"))
      (node (ref "D3") (pin "2") (pinfunction "K_2") (pintype "passive"))
      (node (ref "D4") (pin "2") (pinfunction "K_2") (pintype "passive"))
      (node (ref "D5") (pin "2") (pinfunction "K_2") (pintype "passive"))
      (node (ref "D6") (pin "2") (pinfunction "K_2") (pintype "passive"))
      (node (ref "LED11") (pin "1") (pinfunction "A_1") (pintype "passive"))
      (node (ref "LED12") (pin "1") (pinfunction "A_1") (pintype "passive"))
      (node (ref "LED3") (pin "1") (pinfunction "A_1") (pintype "passive"))
      (node (ref "LED4") (pin "1") (pinfunction "A_1") (pintype "passive"))
      (node (ref "LED7") (pin "1") (pinfunction "A_1") (pintype "passive"))
      (node (ref "LED8") (pin "1") (pinfunction "A_1") (pintype "passive"))
      (node (ref "RL1") (pin "3") (pinfunction "3_3") (pintype "passive"))
      (node (ref "RL2") (pin "3") (pinfunction "3_3") (pintype "passive"))
      (node (ref "RL3") (pin "3") (pinfunction "3_3") (pintype "passive"))
      (node (ref "RL4") (pin "3") (pinfunction "3_3") (pintype "passive"))
      (node (ref "RL5") (pin "3") (pinfunction "3_3") (pintype "passive"))
      (node (ref "RL6") (pin "3") (pinfunction "3_3") (pintype "passive"))
      (node (ref "U1") (pin "4") (pinfunction "C_4") (pintype "passive"))
      (node (ref "U2") (pin "4") (pinfunction "C_4") (pintype "passive"))
      (node (ref "U3") (pin "4") (pinfunction "C_4") (pintype "passive"))
      (node (ref "U4") (pin "4") (pinfunction "C_4") (pintype "passive"))
      (node (ref "U5") (pin "4") (pinfunction "C_4") (pintype "passive"))
      (node (ref "U6") (pin "4") (pinfunction "C_4") (pintype "passive"))
      (node (ref "UN1") (pin "3") (pinfunction "OUT_3") (pintype "power_in"))
    )
    (net (code "77") (name "VCC5_ISO") (class "Default")
      (node (ref "B1") (pin "4") (pinfunction "+VO_4") (pintype "passive"))
      (node (ref "C16") (pin "3") (pinfunction "3_3") (pintype "passive"))
      (node (ref "C17") (pin "3") (pinfunction "3_3") (pintype "passive"))
      (node (ref "C18") (pin "3") (pinfunction "3_3") (pintype "passive"))
      (node (ref "C19") (pin "4") (pinfunction "4_4") (pintype "passive"))
      (node (ref "C6") (pin "1") (pinfunction "1_1") (pintype "passive"))
      (node (ref "LED1") (pin "1") (pinfunction "A_1") (pintype "passive"))
      (node (ref "LED10") (pin "1") (pinfunction "A_1") (pintype "passive"))
      (node (ref "LED2") (pin "1") (pinfunction "A_1") (pintype "passive"))
      (node (ref "LED5") (pin "1") (pinfunction "A_1") (pintype "passive"))
      (node (ref "LED6") (pin "1") (pinfunction "A_1") (pintype "passive"))
      (node (ref "LED9") (pin "1") (pinfunction "A_1") (pintype "passive"))
      (node (ref "R1") (pin "2") (pinfunction "2_2") (pintype "passive"))
      (node (ref "R13") (pin "2") (pinfunction "2_2") (pintype "passive"))
      (node (ref "R14") (pin "2") (pinfunction "2_2") (pintype "passive"))
      (node (ref "R2") (pin "2") (pinfunction "2_2") (pintype "passive"))
      (node (ref "R25") (pin "2") (pinfunction "2_2") (pintype "passive"))
      (node (ref "R26") (pin "2") (pinfunction "2_2") (pintype "passive"))
      (node (ref "U7") (pin "15") (pinfunction "VIN_15") (pintype "passive"))
    )
    (net (code "78") (name "VCC33_ISO") (class "Default")
      (node (ref "C10") (pin "3") (pinfunction "3_3") (pintype "passive"))
      (node (ref "C11") (pin "3") (pinfunction "3_3") (pintype "passive"))
      (node (ref "C14") (pin "3") (pinfunction "3_3") (pintype "passive"))
      (node (ref "C15") (pin "3") (pinfunction "3_3") (pintype "passive"))
      (node (ref "U7") (pin "16") (pinfunction "3V3_16") (pintype "passive"))
    )
    (net (code "79") (name "unconnected-(RL1-Pad2)") (class "Default")
      (node (ref "RL1") (pin "2") (pinfunction "2_2") (pintype "passive+no_connect"))
    )
    (net (code "80") (name "unconnected-(RL2-Pad2)") (class "Default")
      (node (ref "RL2") (pin "2") (pinfunction "2_2") (pintype "passive+no_connect"))
    )
    (net (code "81") (name "unconnected-(RL3-Pad2)") (class "Default")
      (node (ref "RL3") (pin "2") (pinfunction "2_2") (pintype "passive+no_connect"))
    )
    (net (code "82") (name "unconnected-(RL4-Pad2)") (class "Default")
      (node (ref "RL4") (pin "2") (pinfunction "2_2") (pintype "passive+no_connect"))
    )
    (net (code "83") (name "unconnected-(RL5-Pad2)") (class "Default")
      (node (ref "RL5") (pin "2") (pinfunction "2_2") (pintype "passive+no_connect"))
    )
    (net (code "84") (name "unconnected-(RL6-Pad2)") (class "Default")
      (node (ref "RL6") (pin "2") (pinfunction "2_2") (pintype "passive+no_connect"))
    )
    (net (code "85") (name "unconnected-(U7-D2-Pad19)") (class "Default")
      (node (ref "U7") (pin "19") (pinfunction "D2_19") (pintype "passive+no_connect"))
    )
    (net (code "86") (name "unconnected-(U7-EN-Pad1)") (class "Default")
      (node (ref "U7") (pin "1") (pinfunction "EN_1") (pintype "passive+no_connect"))
    )
    (net (code "87") (name "unconnected-(U7-RX0-Pad27)") (class "Default")
      (node (ref "U7") (pin "27") (pinfunction "RX0_27") (pintype "passive+no_connect"))
    )
    (net (code "88") (name "unconnected-(U7-TX0-Pad28)") (class "Default")
      (node (ref "U7") (pin "28") (pinfunction "TX0_28") (pintype "passive+no_connect"))
    )
  )
)
